# Pluvion_1_-_Rev_C.net
KiCad netlist of a schematic drawn in EAGLE
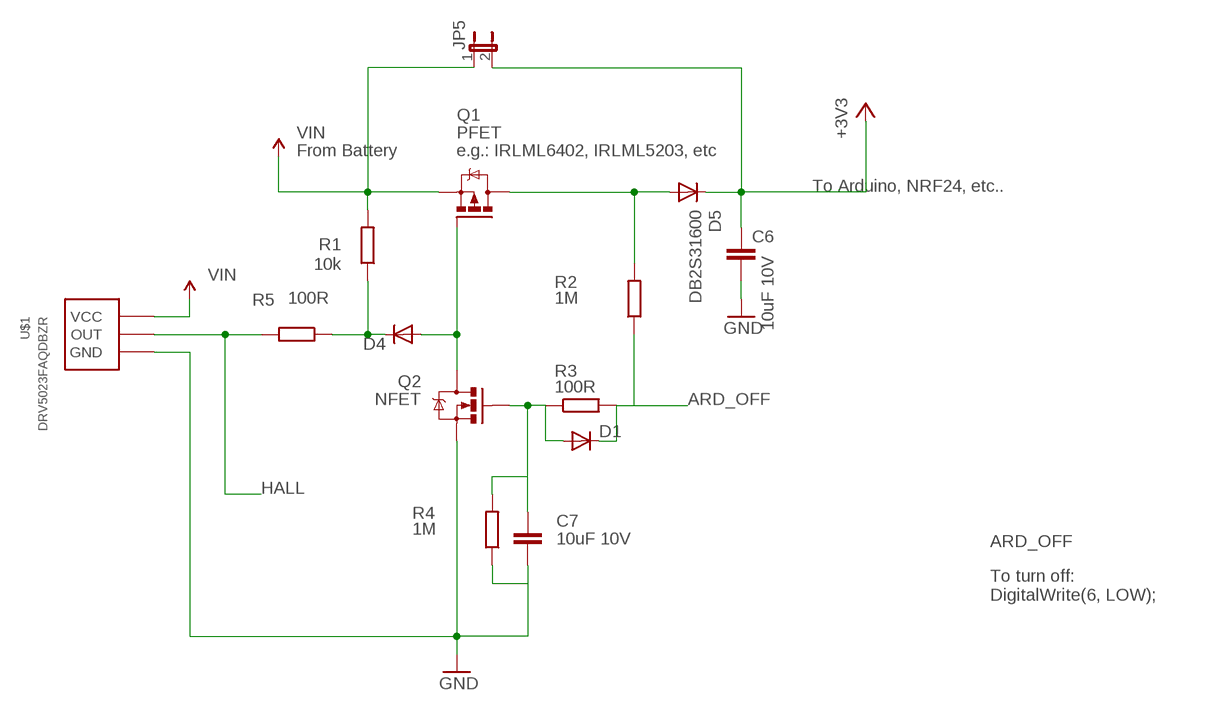
[diagram p0: schematic, sheet 1]
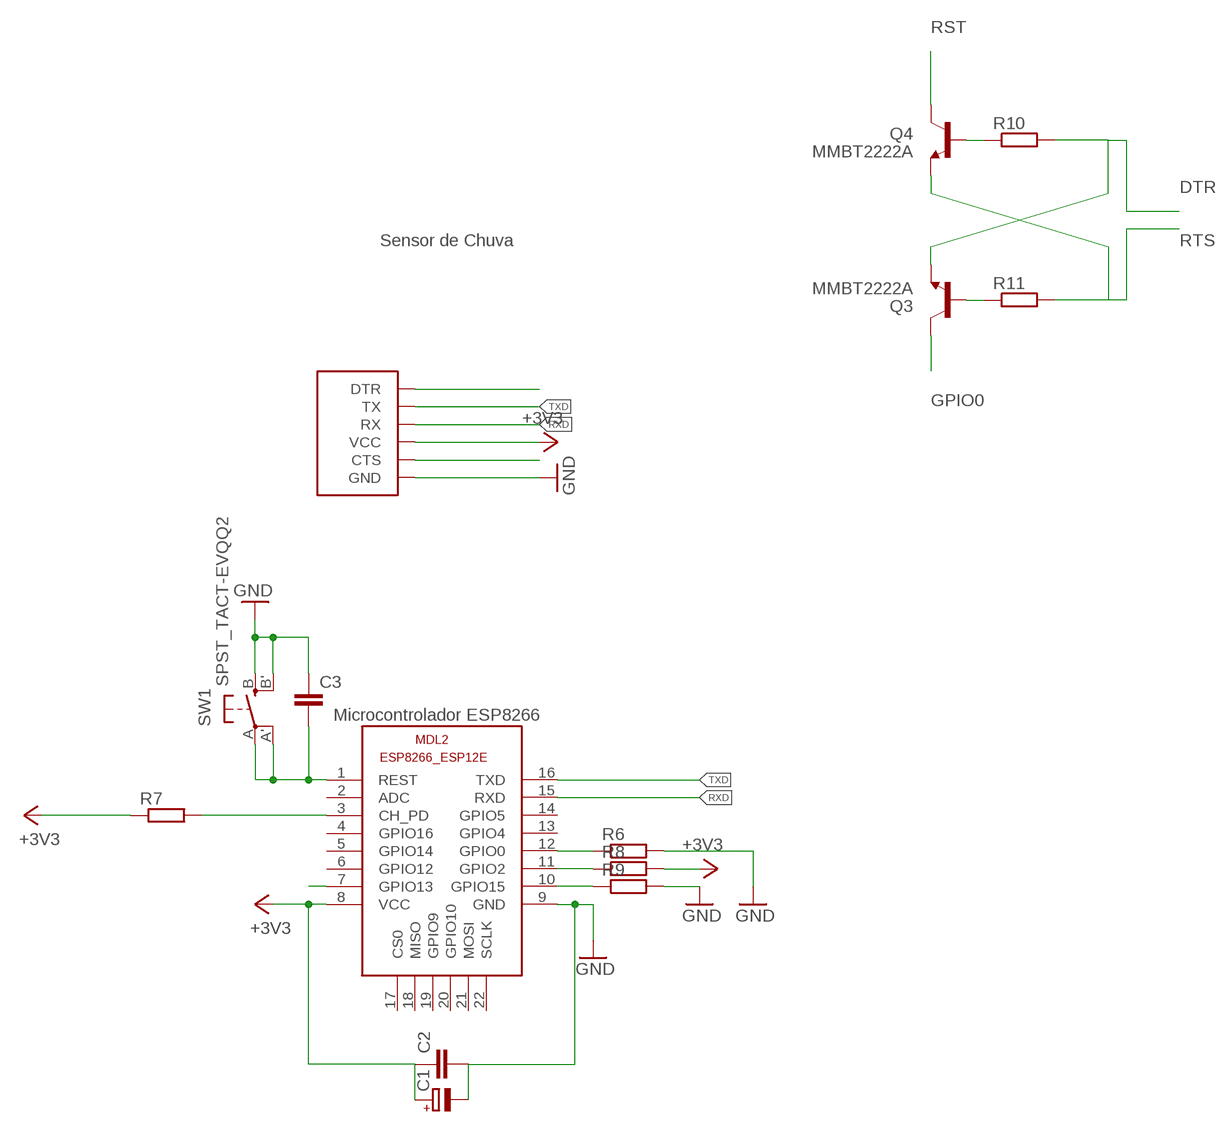
[diagram p1: schematic, sheet 3]

(export (version "E")
  (design (tool "Eeschema 10.0.6"))
  (components
    (comp (ref "C6")
      (value "10uF 10V")
      (footprint "eagle-import:C0805")
      (libsource (lib "eagle-import") (part "C-EUC0805"))
    )
    (comp (ref "C7")
      (value "10uF 10V")
      (footprint "eagle-import:C0805")
      (libsource (lib "eagle-import") (part "C-EUC0805"))
    )
    (comp (ref "D1")
      (value "DIODESMB")
      (footprint "eagle-import:SMB-DIODE")
      (libsource (lib "eagle-import") (part "DIODESMB"))
    )
    (comp (ref "D4")
      (value "DIODESMB")
      (footprint "eagle-import:SMB-DIODE")
      (libsource (lib "eagle-import") (part "DIODESMB"))
    )
    (comp (ref "D5")
      (value "DB2S31600")
      (footprint "eagle-import:SMB-DIODE")
      (libsource (lib "eagle-import") (part "DIODESMB"))
    )
    (comp (ref "JP5")
      (value "JUMPER-2PTH")
      (footprint "eagle-import:1X02")
      (libsource (lib "eagle-import") (part "JUMPER-2PTH"))
    )
    (comp (ref "Q1")
      (value "PFET")
      (footprint "eagle-import:MICRO3")
      (libsource (lib "eagle-import") (part "IRLML5203"))
    )
    (comp (ref "Q2")
      (value "NFET")
      (footprint "eagle-import:SOT23")
      (libsource (lib "eagle-import") (part "MOSFET-NCHANNELBSS123LT1G"))
    )
    (comp (ref "R1")
      (value "10k")
      (footprint "eagle-import:R0805")
      (libsource (lib "eagle-import") (part "R-EU_R0805"))
    )
    (comp (ref "R2")
      (value "1M")
      (footprint "eagle-import:R0805")
      (libsource (lib "eagle-import") (part "R-EU_R0805"))
    )
    (comp (ref "R3")
      (value "100R")
      (footprint "eagle-import:R0805")
      (libsource (lib "eagle-import") (part "R-EU_R0805"))
    )
    (comp (ref "R4")
      (value "1M")
      (footprint "eagle-import:R0805")
      (libsource (lib "eagle-import") (part "R-EU_R0805"))
    )
    (comp (ref "R5")
      (value "100R")
      (footprint "eagle-import:R0805")
      (libsource (lib "eagle-import") (part "R-EU_R0805"))
    )
    (comp (ref "U$1")
      (value "DRV5023FAQDBZR")
      (footprint "eagle-import:SOT23")
      (libsource (lib "eagle-import") (part "DRV5023FAQDBZR"))
    )
    (comp (ref "C1")
      (value "CPOL-EUC")
      (footprint "eagle-import:PANASONIC_C")
      (libsource (lib "eagle-import") (part "CPOL-EUC"))
    )
    (comp (ref "C2")
      (value "C-EUC0805")
      (footprint "eagle-import:C0805")
      (libsource (lib "eagle-import") (part "C-EUC0805"))
    )
    (comp (ref "C3")
      (value "C-EUC0805")
      (footprint "eagle-import:C0805")
      (libsource (lib "eagle-import") (part "C-EUC0805"))
    )
    (comp (ref "MDL2")
      (value "ESP8266-12EESP8266-ESP12E")
      (footprint "eagle-import:ESP8266-ESP12E")
      (libsource (lib "eagle-import") (part "ESP8266-12EESP8266-ESP12E"))
    )
    (comp (ref "Q3")
      (value "MMBT2222A")
      (footprint "eagle-import:SOT23")
      (libsource (lib "eagle-import") (part "TRANSISTOR_NPNMMBT2222A"))
    )
    (comp (ref "Q4")
      (value "MMBT2222A")
      (footprint "eagle-import:SOT23")
      (libsource (lib "eagle-import") (part "TRANSISTOR_NPNMMBT2222A"))
    )
    (comp (ref "R6")
      (value "R-EU_R0805")
      (footprint "eagle-import:R0805")
      (libsource (lib "eagle-import") (part "R-EU_R0805"))
    )
    (comp (ref "R7")
      (value "R-EU_R0805")
      (footprint "eagle-import:R0805")
      (libsource (lib "eagle-import") (part "R-EU_R0805"))
    )
    (comp (ref "R8")
      (value "R-EU_R0805")
      (footprint "eagle-import:R0805")
      (libsource (lib "eagle-import") (part "R-EU_R0805"))
    )
    (comp (ref "R9")
      (value "R-EU_R0805")
      (footprint "eagle-import:R0805")
      (libsource (lib "eagle-import") (part "R-EU_R0805"))
    )
    (comp (ref "R10")
      (value "R-EU_R0805")
      (footprint "eagle-import:R0805")
      (libsource (lib "eagle-import") (part "R-EU_R0805"))
    )
    (comp (ref "R11")
      (value "R-EU_R0805")
      (footprint "eagle-import:R0805")
      (libsource (lib "eagle-import") (part "R-EU_R0805"))
    )
    (comp (ref "SW1")
      (value "SPST_TACT-EVQQ2")
      (footprint "eagle-import:EVQ-Q2")
      (libsource (lib "eagle-import") (part "SPST_TACT-EVQQ2"))
    )
    (comp (ref "U$2")
      (value "FTDI_HEADERSMD")
      (footprint "eagle-import:FTDI_HEADER_SMD")
      (libsource (lib "eagle-import") (part "FTDI_HEADERSMD"))
    )
  )
  (nets
    (net (code "1") (name "+3V3") (class "Default")
      (node (ref "C1") (pin "+") (pinfunction "+_+") (pintype "passive"))
      (node (ref "C2") (pin "1") (pinfunction "1_1") (pintype "passive"))
      (node (ref "C6") (pin "1") (pinfunction "1_1") (pintype "passive"))
      (node (ref "D5") (pin "C") (pinfunction "C_C") (pintype "passive"))
      (node (ref "JP5") (pin "2") (pinfunction "2_2") (pintype "passive"))
      (node (ref "MDL2") (pin "8") (pinfunction "VCC_8") (pintype "bidirectional"))
      (node (ref "R7") (pin "1") (pinfunction "1_1") (pintype "passive"))
      (node (ref "R8") (pin "2") (pinfunction "2_2") (pintype "passive"))
      (node (ref "U$2") (pin "VCC") (pinfunction "VCC_VCC") (pintype "bidirectional"))
    )
    (net (code "2") (name "ARD_OFF") (class "Default")
      (node (ref "D1") (pin "C") (pinfunction "C_C") (pintype "passive"))
      (node (ref "MDL2") (pin "7") (pinfunction "GPIO13_7") (pintype "bidirectional"))
      (node (ref "R2") (pin "1") (pinfunction "1_1") (pintype "passive"))
      (node (ref "R3") (pin "2") (pinfunction "2_2") (pintype "passive"))
    )
    (net (code "3") (name "DTR") (class "Default")
      (node (ref "Q3") (pin "2") (pinfunction "E_2") (pintype "passive"))
      (node (ref "R10") (pin "2") (pinfunction "2_2") (pintype "passive"))
      (node (ref "U$2") (pin "DTR") (pinfunction "DTR_DTR") (pintype "bidirectional"))
    )
    (net (code "4") (name "GND") (class "Default")
      (node (ref "C1") (pin "-") (pinfunction "-_-") (pintype "passive"))
      (node (ref "C2") (pin "2") (pinfunction "2_2") (pintype "passive"))
      (node (ref "C3") (pin "1") (pinfunction "1_1") (pintype "passive"))
      (node (ref "C6") (pin "2") (pinfunction "2_2") (pintype "passive"))
      (node (ref "C7") (pin "2") (pinfunction "2_2") (pintype "passive"))
      (node (ref "MDL2") (pin "9") (pinfunction "GND_9") (pintype "bidirectional"))
      (node (ref "Q2") (pin "2") (pinfunction "S_2") (pintype "passive"))
      (node (ref "R4") (pin "1") (pinfunction "1_1") (pintype "passive"))
      (node (ref "R6") (pin "2") (pinfunction "2_2") (pintype "passive"))
      (node (ref "R9") (pin "2") (pinfunction "2_2") (pintype "passive"))
      (node (ref "SW1") (pin "B") (pinfunction "S_B") (pintype "passive"))
      (node (ref "SW1") (pin "B'") (pinfunction "S1_B'") (pintype "passive"))
      (node (ref "U$1") (pin "3") (pinfunction "GND_3") (pintype "bidirectional"))
      (node (ref "U$2") (pin "GND") (pinfunction "GND_GND") (pintype "bidirectional"))
    )
    (net (code "5") (name "GPIO0") (class "Default")
      (node (ref "MDL2") (pin "12") (pinfunction "GPIO0_12") (pintype "bidirectional"))
      (node (ref "Q3") (pin "3") (pinfunction "C_3") (pintype "passive"))
      (node (ref "R6") (pin "1") (pinfunction "1_1") (pintype "passive"))
    )
    (net (code "6") (name "HALL") (class "Default")
      (node (ref "R5") (pin "2") (pinfunction "2_2") (pintype "passive"))
      (node (ref "U$1") (pin "2") (pinfunction "OUT_2") (pintype "bidirectional"))
    )
    (net (code "7") (name "Net-(D4-PadC)") (class "Default")
      (node (ref "D4") (pin "C") (pinfunction "C_C") (pintype "passive"))
      (node (ref "R1") (pin "1") (pinfunction "1_1") (pintype "passive"))
      (node (ref "R5") (pin "1") (pinfunction "1_1") (pintype "passive"))
    )
    (net (code "8") (name "Net-(MDL2-CH_PD)") (class "Default")
      (node (ref "MDL2") (pin "3") (pinfunction "CH_PD_3") (pintype "bidirectional"))
      (node (ref "R7") (pin "2") (pinfunction "2_2") (pintype "passive"))
    )
    (net (code "9") (name "Net-(MDL2-GPIO2)") (class "Default")
      (node (ref "MDL2") (pin "11") (pinfunction "GPIO2_11") (pintype "bidirectional"))
      (node (ref "R8") (pin "1") (pinfunction "1_1") (pintype "passive"))
    )
    (net (code "10") (name "Net-(MDL2-GPIO15)") (class "Default")
      (node (ref "MDL2") (pin "10") (pinfunction "GPIO15_10") (pintype "bidirectional"))
      (node (ref "R9") (pin "1") (pinfunction "1_1") (pintype "passive"))
    )
    (net (code "11") (name "Net-(MDL2-REST)") (class "Default")
      (node (ref "C3") (pin "2") (pinfunction "2_2") (pintype "passive"))
      (node (ref "MDL2") (pin "1") (pinfunction "REST_1") (pintype "bidirectional"))
      (node (ref "SW1") (pin "A") (pinfunction "P_A") (pintype "passive"))
      (node (ref "SW1") (pin "A'") (pinfunction "P1_A'") (pintype "passive"))
    )
    (net (code "12") (name "Net-(Q1-D)") (class "Default")
      (node (ref "D5") (pin "A") (pinfunction "A_A") (pintype "passive"))
      (node (ref "Q1") (pin "3") (pinfunction "D_3") (pintype "passive"))
      (node (ref "R2") (pin "2") (pinfunction "2_2") (pintype "passive"))
    )
    (net (code "13") (name "Net-(Q1-G)") (class "Default")
      (node (ref "D4") (pin "A") (pinfunction "A_A") (pintype "passive"))
      (node (ref "Q1") (pin "1") (pinfunction "G_1") (pintype "passive"))
      (node (ref "Q2") (pin "3") (pinfunction "D_3") (pintype "passive"))
    )
    (net (code "14") (name "Net-(Q2-G)") (class "Default")
      (node (ref "C7") (pin "1") (pinfunction "1_1") (pintype "passive"))
      (node (ref "D1") (pin "A") (pinfunction "A_A") (pintype "passive"))
      (node (ref "Q2") (pin "1") (pinfunction "G_1") (pintype "passive"))
      (node (ref "R3") (pin "1") (pinfunction "1_1") (pintype "passive"))
      (node (ref "R4") (pin "2") (pinfunction "2_2") (pintype "passive"))
    )
    (net (code "15") (name "Net-(Q3-B)") (class "Default")
      (node (ref "Q3") (pin "1") (pinfunction "B_1") (pintype "passive"))
      (node (ref "R11") (pin "1") (pinfunction "1_1") (pintype "passive"))
    )
    (net (code "16") (name "Net-(Q4-B)") (class "Default")
      (node (ref "Q4") (pin "1") (pinfunction "B_1") (pintype "passive"))
      (node (ref "R10") (pin "1") (pinfunction "1_1") (pintype "passive"))
    )
    (net (code "17") (name "RST") (class "Default")
      (node (ref "Q4") (pin "3") (pinfunction "C_3") (pintype "passive"))
    )
    (net (code "18") (name "RTS") (class "Default")
      (node (ref "Q4") (pin "2") (pinfunction "E_2") (pintype "passive"))
      (node (ref "R11") (pin "2") (pinfunction "2_2") (pintype "passive"))
      (node (ref "U$2") (pin "CTS") (pinfunction "CTS_CTS") (pintype "bidirectional"))
    )
    (net (code "19") (name "RXD") (class "Default")
      (node (ref "MDL2") (pin "15") (pinfunction "RXD_15") (pintype "bidirectional"))
      (node (ref "U$2") (pin "RX") (pinfunction "RX_RX") (pintype "bidirectional"))
    )
    (net (code "20") (name "TXD") (class "Default")
      (node (ref "MDL2") (pin "16") (pinfunction "TXD_16") (pintype "bidirectional"))
      (node (ref "U$2") (pin "TX") (pinfunction "TX_TX") (pintype "bidirectional"))
    )
    (net (code "21") (name "VIN") (class "Default")
      (node (ref "JP5") (pin "1") (pinfunction "1_1") (pintype "passive"))
      (node (ref "Q1") (pin "2") (pinfunction "S_2") (pintype "passive"))
      (node (ref "R1") (pin "2") (pinfunction "2_2") (pintype "passive"))
      (node (ref "U$1") (pin "1") (pinfunction "VCC_1") (pintype "bidirectional"))
    )
    (net (code "22") (name "unconnected-(MDL2-ADC-Pad2)") (class "Default")
      (node (ref "MDL2") (pin "2") (pinfunction "ADC_2") (pintype "bidirectional"))
    )
    (net (code "23") (name "unconnected-(MDL2-CS0-Pad17)") (class "Default")
      (node (ref "MDL2") (pin "17") (pinfunction "CS0_17") (pintype "bidirectional"))
    )
    (net (code "24") (name "unconnected-(MDL2-GPIO4-Pad13)") (class "Default")
      (node (ref "MDL2") (pin "13") (pinfunction "GPIO4_13") (pintype "bidirectional"))
    )
    (net (code "25") (name "unconnected-(MDL2-GPIO5-Pad14)") (class "Default")
      (node (ref "MDL2") (pin "14") (pinfunction "GPIO5_14") (pintype "bidirectional"))
    )
    (net (code "26") (name "unconnected-(MDL2-GPIO9-Pad19)") (class "Default")
      (node (ref "MDL2") (pin "19") (pinfunction "GPIO9_19") (pintype "bidirectional"))
    )
    (net (code "27") (name "unconnected-(MDL2-GPIO10-Pad20)") (class "Default")
      (node (ref "MDL2") (pin "20") (pinfunction "GPIO10_20") (pintype "bidirectional"))
    )
    (net (code "28") (name "unconnected-(MDL2-GPIO12-Pad6)") (class "Default")
      (node (ref "MDL2") (pin "6") (pinfunction "GPIO12_6") (pintype "bidirectional"))
    )
    (net (code "29") (name "unconnected-(MDL2-GPIO14-Pad5)") (class "Default")
      (node (ref "MDL2") (pin "5") (pinfunction "GPIO14_5") (pintype "bidirectional"))
    )
    (net (code "30") (name "unconnected-(MDL2-GPIO16-Pad4)") (class "Default")
      (node (ref "MDL2") (pin "4") (pinfunction "GPIO16_4") (pintype "bidirectional"))
    )
    (net (code "31") (name "unconnected-(MDL2-MISO-Pad18)") (class "Default")
      (node (ref "MDL2") (pin "18") (pinfunction "MISO_18") (pintype "bidirectional"))
    )
    (net (code "32") (name "unconnected-(MDL2-MOSI-Pad21)") (class "Default")
      (node (ref "MDL2") (pin "21") (pinfunction "MOSI_21") (pintype "bidirectional"))
    )
    (net (code "33") (name "unconnected-(MDL2-SCLK-Pad22)") (class "Default")
      (node (ref "MDL2") (pin "22") (pinfunction "SCLK_22") (pintype "bidirectional"))
    )
  )
)
